# PainRegister_Power.net
KiCad netlist of a schematic drawn in Altium Designer
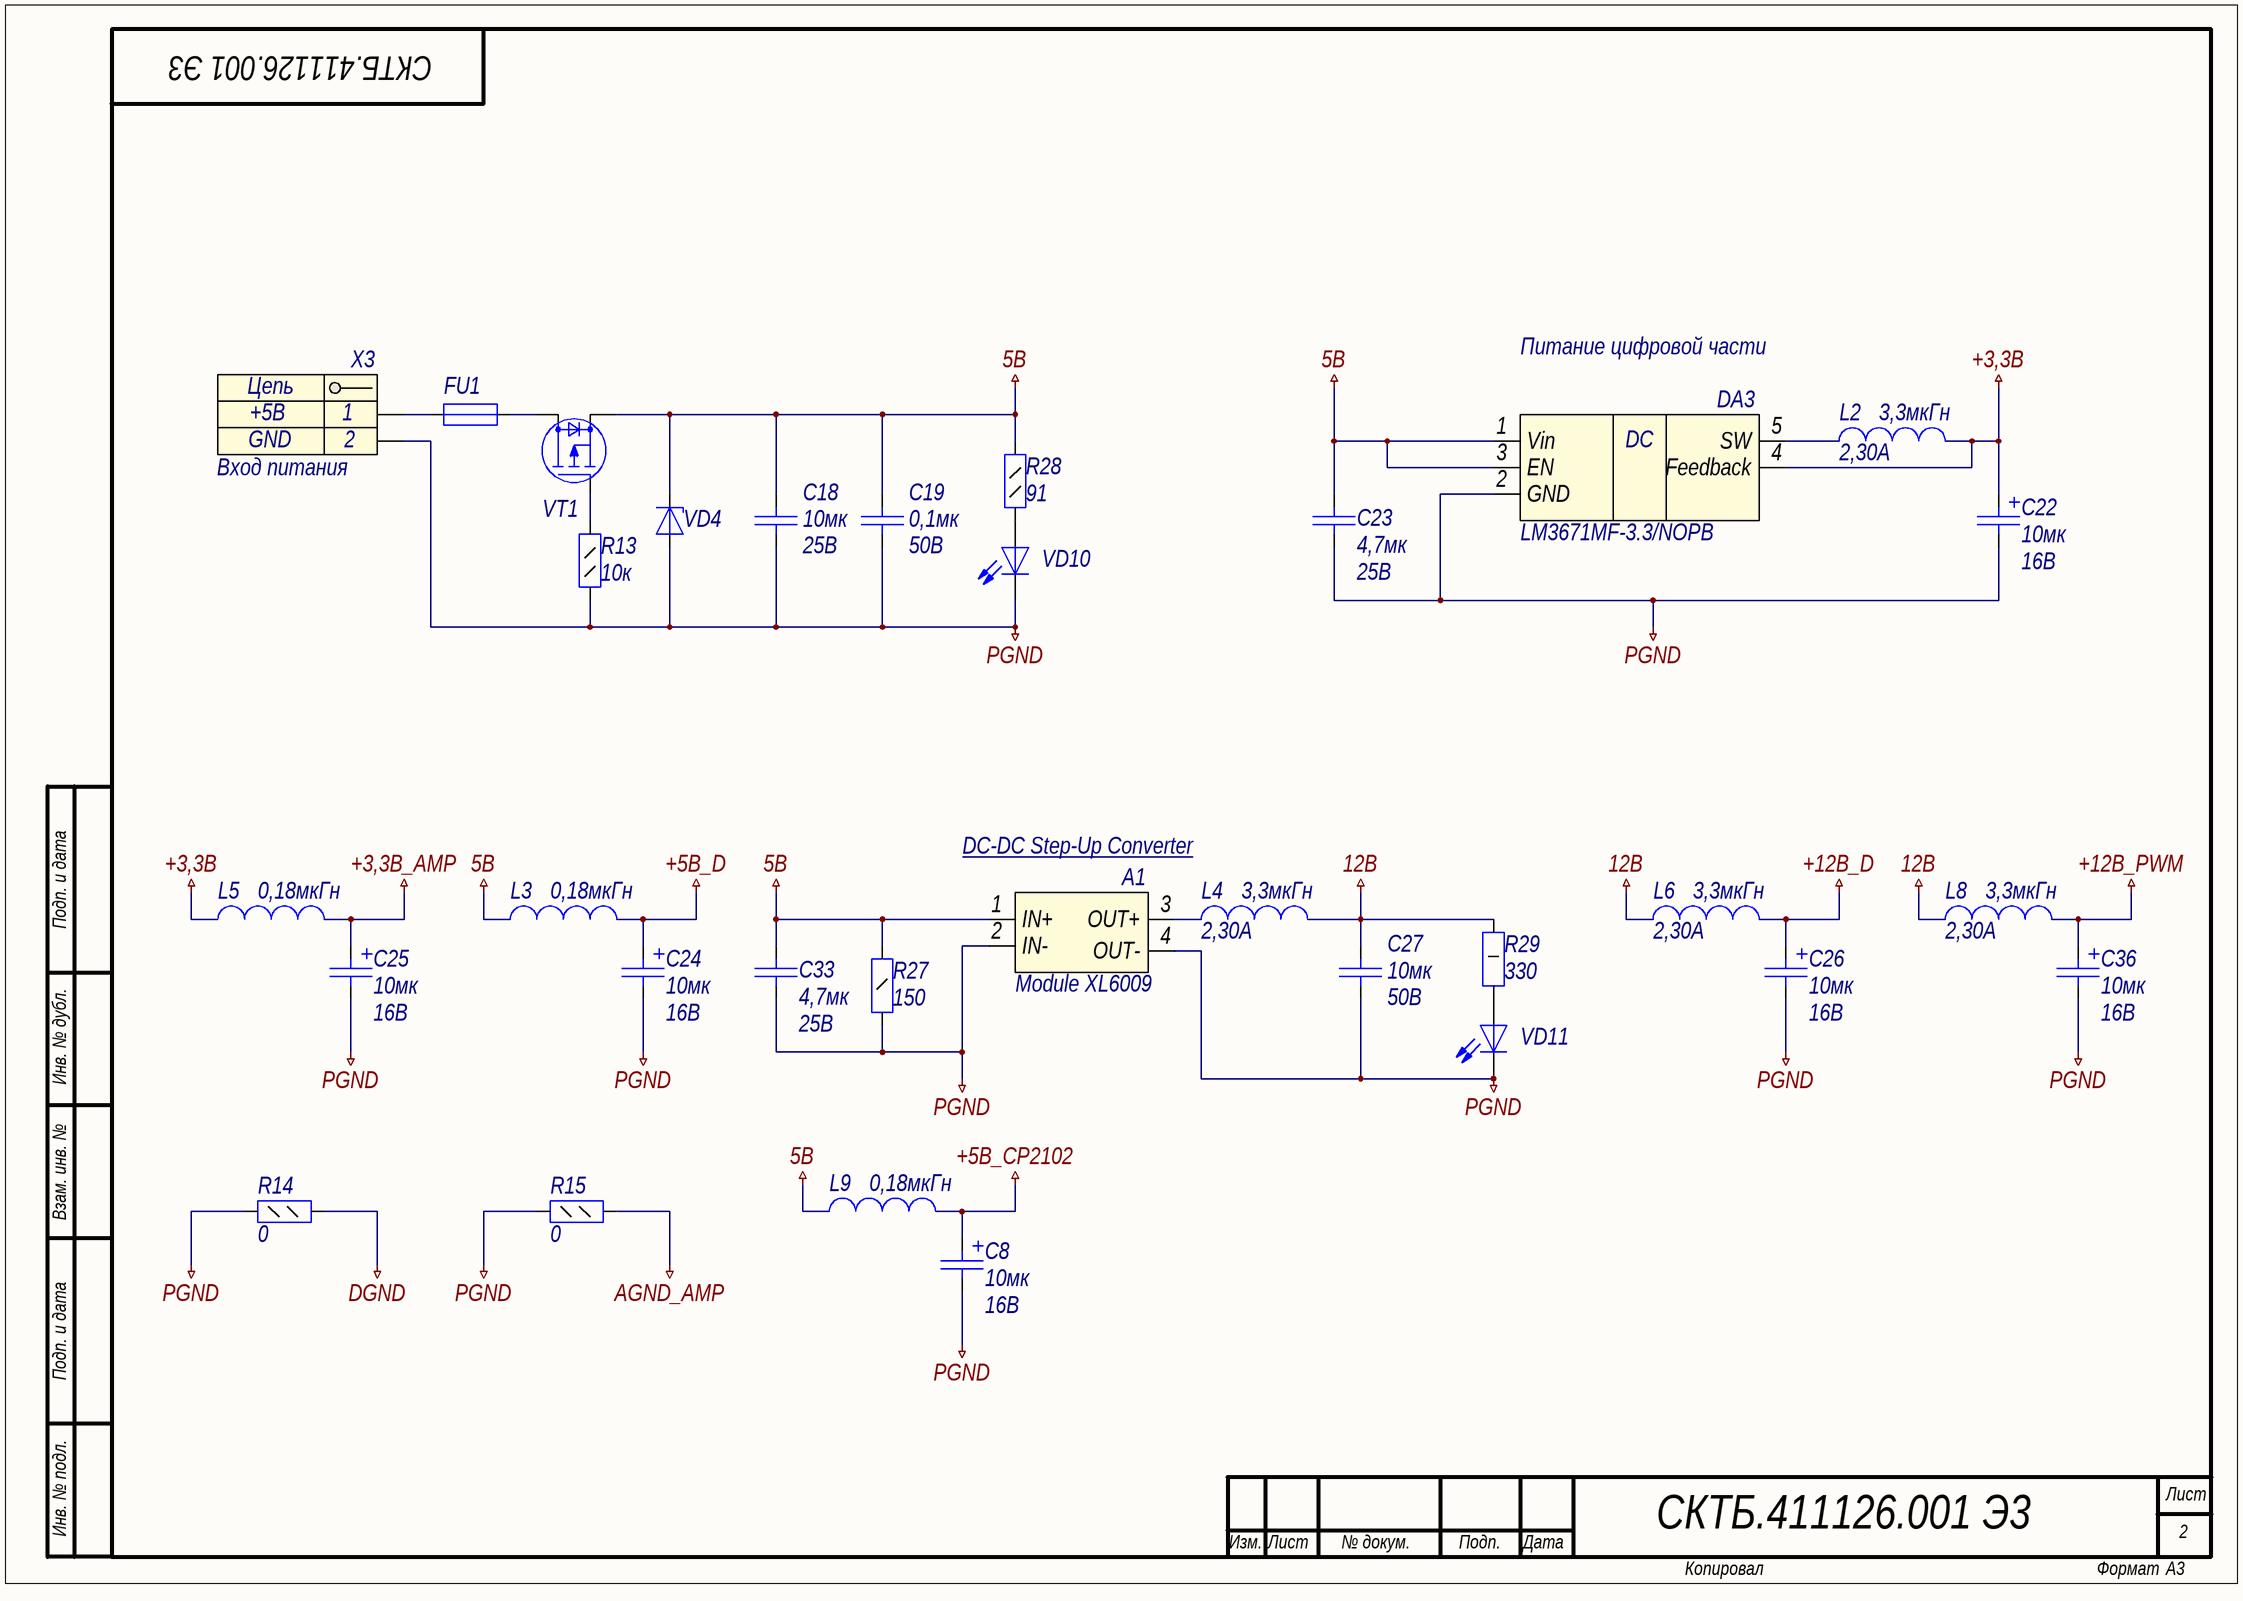
[diagram p0: PainRegister_Power.SchDoc]

(export (version "E")
  (design (tool "Eeschema 10.0.6"))
  (components
    (comp (ref "A1")
      (value "Module XL6009")
      (footprint "Module XL6009")
      (description "DC-DC step-up converter for 5/32-V to 5/35-V")
      (libsource (lib "MOP44") (part "Module XL6009"))
    )
    (comp (ref "C8")
      (value "10мк")
      (footprint "TANTAL CASE A")
      (description "Конденсатор полярный")
      (fields
        (field (name "VOLTAGE") "16В")
        (field (name "PART NUMBER") "293D106X9016A2TE3")
        (field (name "Comment") "Capacitor_pol")
      )
      (libsource (lib "MOP44") (part "Capacitor_pol"))
    )
    (comp (ref "C18")
      (value "10мк")
      (footprint "C1206")
      (description "Конденсатор")
      (fields
        (field (name "VOLTAGE") "25В")
        (field (name "PART NUMBER") "GRM31CR71E106KA12L*")
        (field (name "Comment") "Capacitor")
      )
      (libsource (lib "MOP44") (part "Capacitor"))
    )
    (comp (ref "C19")
      (value "0,1мк")
      (footprint "C0805")
      (description "Конденсатор")
      (fields
        (field (name "VOLTAGE") "50В")
        (field (name "PART NUMBER") "GRM21BR71H104KA01L ")
        (field (name "Comment") "Capacitor")
      )
      (libsource (lib "MOP44") (part "Capacitor"))
    )
    (comp (ref "C22")
      (value "10мк")
      (footprint "TANTAL CASE A")
      (description "Конденсатор полярный")
      (fields
        (field (name "VOLTAGE") "16В")
        (field (name "PART NUMBER") "293D106X9016A2TE3")
        (field (name "Comment") "Capacitor_pol")
      )
      (libsource (lib "MOP44") (part "Capacitor_pol"))
    )
    (comp (ref "C23")
      (value "4,7мк")
      (footprint "C0805")
      (description "Конденсатор")
      (fields
        (field (name "VOLTAGE") "25B")
        (field (name "PART NUMBER") "GRM21BR61E475KA12L")
        (field (name "Comment") "Capacitor")
      )
      (libsource (lib "MOP44") (part "Capacitor"))
    )
    (comp (ref "C24")
      (value "10мк")
      (footprint "TANTAL CASE A")
      (description "Конденсатор полярный")
      (fields
        (field (name "VOLTAGE") "16В")
        (field (name "PART NUMBER") "293D106X9016A2TE3")
        (field (name "Comment") "Capacitor_pol")
      )
      (libsource (lib "MOP44") (part "Capacitor_pol"))
    )
    (comp (ref "C25")
      (value "10мк")
      (footprint "TANTAL CASE A")
      (description "Конденсатор полярный")
      (fields
        (field (name "VOLTAGE") "16В")
        (field (name "PART NUMBER") "293D106X9016A2TE3")
        (field (name "Comment") "Capacitor_pol")
      )
      (libsource (lib "MOP44") (part "Capacitor_pol"))
    )
    (comp (ref "C26")
      (value "10мк")
      (footprint "TANTAL CASE A")
      (description "Конденсатор полярный")
      (fields
        (field (name "VOLTAGE") "16В")
        (field (name "PART NUMBER") "293D106X9016A2TE3")
        (field (name "Comment") "Capacitor_pol")
      )
      (libsource (lib "MOP44") (part "Capacitor_pol"))
    )
    (comp (ref "C27")
      (value "10мк")
      (footprint "C1210")
      (description "Конденсатор")
      (fields
        (field (name "VOLTAGE") "50В")
        (field (name "PART NUMBER") "GRM32ER71H106K")
        (field (name "Comment") "Capacitor")
      )
      (libsource (lib "MOP44") (part "Capacitor"))
    )
    (comp (ref "C33")
      (value "4,7мк")
      (footprint "C0805")
      (description "Конденсатор")
      (fields
        (field (name "VOLTAGE") "25B")
        (field (name "PART NUMBER") "GRM21BR61E475KA12L")
        (field (name "Comment") "Capacitor")
      )
      (libsource (lib "MOP44") (part "Capacitor"))
    )
    (comp (ref "C36")
      (value "10мк")
      (footprint "TANTAL CASE A")
      (description "Конденсатор полярный")
      (fields
        (field (name "VOLTAGE") "16В")
        (field (name "PART NUMBER") "293D106X9016A2TE3")
        (field (name "Comment") "Capacitor_pol")
      )
      (libsource (lib "MOP44") (part "Capacitor_pol"))
    )
    (comp (ref "DA3")
      (value "LM3671MF")
      (footprint "SOT23-5")
      (description "Step-Down DC-DC Converter")
      (fields
        (field (name "PART NUMBER") "LM3671MF-3.3/NOPB")
        (field (name "MANUFACTURER") "Texas Instruments")
      )
      (libsource (lib "MOP44") (part "LM3671MF"))
    )
    (comp (ref "FU1")
      (value "Fuse")
      (footprint "FUSE812")
      (description "Предохранитель")
      (fields (field (name "PART NUMBER") "MF-MSMF260"))
      (libsource (lib "MOP44") (part "Fuse"))
    )
    (comp (ref "L2")
      (value "3,3мкГн")
      (footprint "SRR0604")
      (description "EMI Suppression Filter")
      (fields
        (field (name "RATED CURRENT") "2,30А")
        (field (name "PART NUMBER") "SRR0604-3R3ML")
        (field (name "Comment") "Inductor")
      )
      (libsource (lib "MOP44") (part "Inductor"))
    )
    (comp (ref "L3")
      (value "0,18мкГн")
      (footprint "L0805")
      (description "EMI Suppression Filter")
      (fields (field (name "PART NUMBER") "CM201212-R18KL") (field (name "Comment") "Inductor"))
      (libsource (lib "MOP44") (part "Inductor"))
    )
    (comp (ref "L4")
      (value "3,3мкГн")
      (footprint "SRR0604")
      (description "EMI Suppression Filter")
      (fields
        (field (name "RATED CURRENT") "2,30А")
        (field (name "PART NUMBER") "SRR0604-3R3ML")
        (field (name "Comment") "Inductor")
      )
      (libsource (lib "MOP44") (part "Inductor"))
    )
    (comp (ref "L5")
      (value "0,18мкГн")
      (footprint "L0805")
      (description "EMI Suppression Filter")
      (fields (field (name "PART NUMBER") "CM201212-R18KL") (field (name "Comment") "Inductor"))
      (libsource (lib "MOP44") (part "Inductor"))
    )
    (comp (ref "L6")
      (value "3,3мкГн")
      (footprint "SRR0604")
      (description "EMI Suppression Filter")
      (fields
        (field (name "RATED CURRENT") "2,30А")
        (field (name "PART NUMBER") "SRR0604-3R3ML")
        (field (name "Comment") "Inductor")
      )
      (libsource (lib "MOP44") (part "Inductor"))
    )
    (comp (ref "L8")
      (value "3,3мкГн")
      (footprint "SRR0604")
      (description "EMI Suppression Filter")
      (fields
        (field (name "RATED CURRENT") "2,30А")
        (field (name "PART NUMBER") "SRR0604-3R3ML")
        (field (name "Comment") "Inductor")
      )
      (libsource (lib "MOP44") (part "Inductor"))
    )
    (comp (ref "L9")
      (value "0,18мкГн")
      (footprint "L0805")
      (description "EMI Suppression Filter")
      (fields (field (name "PART NUMBER") "CM201212-R18KL") (field (name "Comment") "Inductor"))
      (libsource (lib "MOP44") (part "Inductor"))
    )
    (comp (ref "R13")
      (value "10к")
      (footprint "R0805")
      (description "Резистор")
      (fields (field (name "PART NUMBER") "RC0805FR-0710KL") (field (name "POWER") "0,125Вт"))
      (libsource (lib "") (part "Resistor_0,125Вт_1"))
    )
    (comp (ref "R14")
      (value "0")
      (footprint "R0805")
      (description "Резистор")
      (fields (field (name "PART NUMBER") "RC0805FR-070RL") (field (name "POWER") "0,125Вт"))
      (libsource (lib "MOP44") (part "Resistor_0,125Вт"))
    )
    (comp (ref "R15")
      (value "0")
      (footprint "R0805")
      (description "Резистор")
      (fields (field (name "PART NUMBER") "RC0805FR-070RL") (field (name "POWER") "0,125Вт"))
      (libsource (lib "MOP44") (part "Resistor_0,125Вт"))
    )
    (comp (ref "R27")
      (value "150")
      (footprint "R1206")
      (description "Резистор")
      (fields (field (name "PART NUMBER") "RC1206FR-07150RL") (field (name "POWER") "0,25Вт"))
      (libsource (lib "MOP44") (part "Resistor_0,25Вт"))
    )
    (comp (ref "R28")
      (value "91")
      (footprint "R0805")
      (description "Резистор")
      (fields (field (name "PART NUMBER") "RC0805FR-0791RL") (field (name "POWER") "0,125Вт"))
      (libsource (lib "") (part "Resistor_0,125Вт_1"))
    )
    (comp (ref "R29")
      (value "330")
      (footprint "R2512")
      (description "Резистор")
      (fields (field (name "PART NUMBER") "RC2512FR-07330RL") (field (name "POWER") "1Вт"))
      (libsource (lib "MOP44") (part "Resistor_1Вт"))
    )
    (comp (ref "VD4")
      (value "DiodeZener")
      (footprint "SMA")
      (description "Cтабилитрон (лавинный выпрямительный диод) односторонний")
      (fields (field (name "PART NUMBER") "SMAJ5.0A"))
      (libsource (lib "MOP44") (part "DiodeZener"))
    )
    (comp (ref "VD10")
      (value "LED")
      (footprint "L_0805")
      (description "Светодиод")
      (fields (field (name "PART NUMBER") "KP-2012EC"))
      (libsource (lib "MOP44") (part "LED"))
    )
    (comp (ref "VD11")
      (value "LED")
      (footprint "L_0805")
      (description "Светодиод")
      (fields (field (name "PART NUMBER") "KP-2012EC"))
      (libsource (lib "MOP44") (part "LED"))
    )
    (comp (ref "VT1")
      (value "P-MOSFET")
      (footprint "SOT23-3")
      (description "N-MOSFET")
      (fields
        (field (name "PART NUMBER") "IRLML6401TRPBF")
        (field (name "MANUFACTURER") "International Rectifier")
      )
      (libsource (lib "MOP44") (part "P-MOSFET"))
    )
    (comp (ref "X3")
      (value "Вход питания")
      (footprint "TERMINAL-2WAY-3.5MM")
      (description "Разъем - 2 конт. клеммник")
      (libsource (lib "MOP44") (part "Header_2_trm"))
    )
  )
  (nets
    (net (code "1") (name "+3,3В") (class "Default")
      (node (ref "C22") (pin "1") (pinfunction "1_1") (pintype "passive"))
      (node (ref "DA3") (pin "4") (pinfunction "Feedback_4") (pintype "power_in"))
      (node (ref "L2") (pin "2") (pinfunction "2_2") (pintype "passive"))
      (node (ref "L5") (pin "1") (pinfunction "1_1") (pintype "passive"))
    )
    (net (code "2") (name "+3,3В_AMP") (class "Default")
      (node (ref "C25") (pin "1") (pinfunction "1_1") (pintype "passive"))
      (node (ref "L5") (pin "2") (pinfunction "2_2") (pintype "passive"))
    )
    (net (code "3") (name "+5B_CP2102") (class "Default")
      (node (ref "C8") (pin "1") (pinfunction "1_1") (pintype "passive"))
      (node (ref "L9") (pin "2") (pinfunction "2_2") (pintype "passive"))
    )
    (net (code "4") (name "+5B_D") (class "Default")
      (node (ref "C24") (pin "1") (pinfunction "1_1") (pintype "passive"))
      (node (ref "L3") (pin "2") (pinfunction "2_2") (pintype "passive"))
    )
    (net (code "5") (name "+12В_D") (class "Default")
      (node (ref "C26") (pin "1") (pinfunction "1_1") (pintype "passive"))
      (node (ref "L6") (pin "2") (pinfunction "2_2") (pintype "passive"))
    )
    (net (code "6") (name "+12В_PWM") (class "Default")
      (node (ref "C36") (pin "1") (pinfunction "1_1") (pintype "passive"))
      (node (ref "L8") (pin "2") (pinfunction "2_2") (pintype "passive"))
    )
    (net (code "7") (name "5B") (class "Default")
      (node (ref "A1") (pin "1") (pinfunction "IN+_1") (pintype "power_in"))
      (node (ref "C18") (pin "2") (pinfunction "2_2") (pintype "passive"))
      (node (ref "C19") (pin "2") (pinfunction "2_2") (pintype "passive"))
      (node (ref "C23") (pin "2") (pinfunction "2_2") (pintype "passive"))
      (node (ref "C33") (pin "2") (pinfunction "2_2") (pintype "passive"))
      (node (ref "DA3") (pin "1") (pinfunction "Vin_1") (pintype "power_in"))
      (node (ref "DA3") (pin "3") (pinfunction "EN_3") (pintype "power_in"))
      (node (ref "L3") (pin "1") (pinfunction "1_1") (pintype "passive"))
      (node (ref "L9") (pin "1") (pinfunction "1_1") (pintype "passive"))
      (node (ref "R27") (pin "2") (pinfunction "2_2") (pintype "passive"))
      (node (ref "R28") (pin "2") (pinfunction "2_2") (pintype "passive"))
      (node (ref "VD4") (pin "1") (pinfunction "K_1") (pintype "passive"))
      (node (ref "VT1") (pin "3") (pinfunction "S_3") (pintype "passive"))
    )
    (net (code "8") (name "12В") (class "Default")
      (node (ref "C27") (pin "2") (pinfunction "2_2") (pintype "passive"))
      (node (ref "L4") (pin "2") (pinfunction "2_2") (pintype "passive"))
      (node (ref "L6") (pin "1") (pinfunction "1_1") (pintype "passive"))
      (node (ref "L8") (pin "1") (pinfunction "1_1") (pintype "passive"))
      (node (ref "R29") (pin "2") (pinfunction "5_2") (pintype "passive"))
    )
    (net (code "9") (name "AGND_AMP") (class "Default")
      (node (ref "R15") (pin "2") (pinfunction "2_2") (pintype "passive"))
    )
    (net (code "10") (name "DGND") (class "Default")
      (node (ref "R14") (pin "2") (pinfunction "2_2") (pintype "passive"))
    )
    (net (code "11") (name "Net-(A1-OUT+)") (class "Default")
      (node (ref "A1") (pin "3") (pinfunction "OUT+_3") (pintype "power_in"))
      (node (ref "L4") (pin "1") (pinfunction "1_1") (pintype "passive"))
    )
    (net (code "12") (name "Net-(DA3-SW)") (class "Default")
      (node (ref "DA3") (pin "5") (pinfunction "SW_5") (pintype "power_in"))
      (node (ref "L2") (pin "1") (pinfunction "1_1") (pintype "passive"))
    )
    (net (code "13") (name "Net-(FU1-Pad1)") (class "Default")
      (node (ref "FU1") (pin "1") (pinfunction "1_1") (pintype "passive"))
      (node (ref "X3") (pin "1") (pinfunction "1_1") (pintype "passive"))
    )
    (net (code "14") (name "Net-(VD10-A)") (class "Default")
      (node (ref "R28") (pin "1") (pinfunction "1_1") (pintype "passive"))
      (node (ref "VD10") (pin "2") (pinfunction "A_2") (pintype "passive"))
    )
    (net (code "15") (name "Net-(VD11-A)") (class "Default")
      (node (ref "R29") (pin "1") (pinfunction "1_1") (pintype "passive"))
      (node (ref "VD11") (pin "2") (pinfunction "A_2") (pintype "passive"))
    )
    (net (code "16") (name "Net-(VT1-D)") (class "Default")
      (node (ref "FU1") (pin "2") (pinfunction "2_2") (pintype "passive"))
      (node (ref "VT1") (pin "2") (pinfunction "D_2") (pintype "passive"))
    )
    (net (code "17") (name "Net-(VT1-G)") (class "Default")
      (node (ref "R13") (pin "2") (pinfunction "2_2") (pintype "passive"))
      (node (ref "VT1") (pin "1") (pinfunction "G_1") (pintype "passive"))
    )
    (net (code "18") (name "PGND") (class "Default")
      (node (ref "A1") (pin "2") (pinfunction "IN-_2") (pintype "power_in"))
      (node (ref "A1") (pin "4") (pinfunction "OUT-_4") (pintype "power_in"))
      (node (ref "C18") (pin "1") (pinfunction "1_1") (pintype "passive"))
      (node (ref "C19") (pin "1") (pinfunction "1_1") (pintype "passive"))
      (node (ref "C22") (pin "2") (pinfunction "2_2") (pintype "passive"))
      (node (ref "C23") (pin "1") (pinfunction "1_1") (pintype "passive"))
      (node (ref "C24") (pin "2") (pinfunction "2_2") (pintype "passive"))
      (node (ref "C25") (pin "2") (pinfunction "2_2") (pintype "passive"))
      (node (ref "C26") (pin "2") (pinfunction "2_2") (pintype "passive"))
      (node (ref "C27") (pin "1") (pinfunction "1_1") (pintype "passive"))
      (node (ref "C33") (pin "1") (pinfunction "1_1") (pintype "passive"))
      (node (ref "C36") (pin "2") (pinfunction "2_2") (pintype "passive"))
      (node (ref "C8") (pin "2") (pinfunction "2_2") (pintype "passive"))
      (node (ref "DA3") (pin "2") (pinfunction "GND_2") (pintype "power_in"))
      (node (ref "R13") (pin "1") (pinfunction "1_1") (pintype "passive"))
      (node (ref "R14") (pin "1") (pinfunction "1_1") (pintype "passive"))
      (node (ref "R15") (pin "1") (pinfunction "1_1") (pintype "passive"))
      (node (ref "R27") (pin "1") (pinfunction "1_1") (pintype "passive"))
      (node (ref "VD10") (pin "1") (pinfunction "K_1") (pintype "passive"))
      (node (ref "VD11") (pin "1") (pinfunction "K_1") (pintype "passive"))
      (node (ref "VD4") (pin "2") (pinfunction "A_2") (pintype "passive"))
      (node (ref "X3") (pin "2") (pinfunction "2_2") (pintype "passive"))
    )
  )
)
